# v5.net
KiCad netlist of a schematic drawn in EAGLE
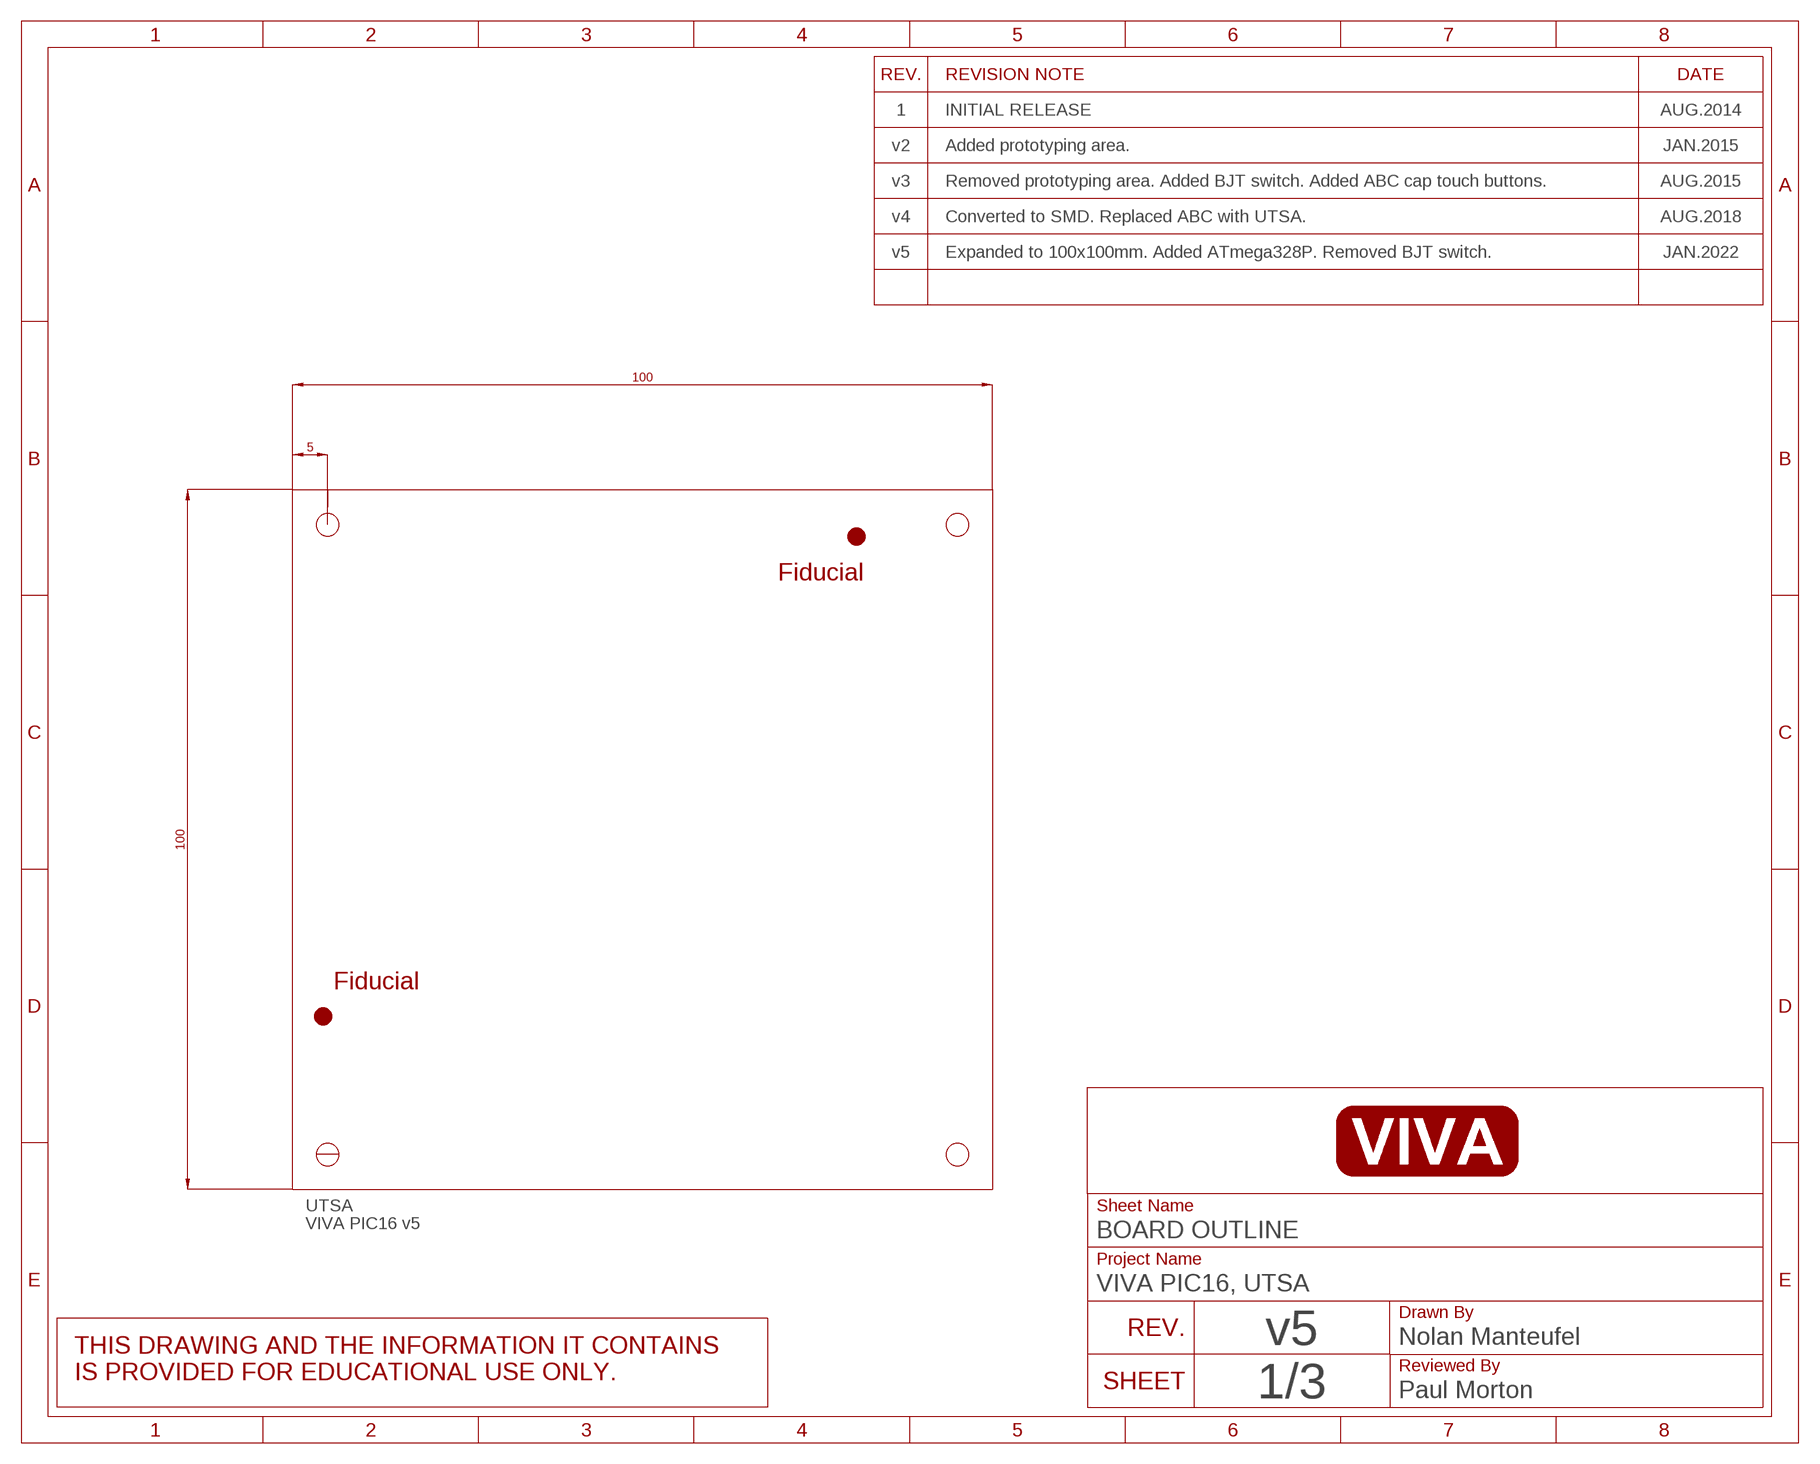
[diagram p0: schematic, sheet 1]
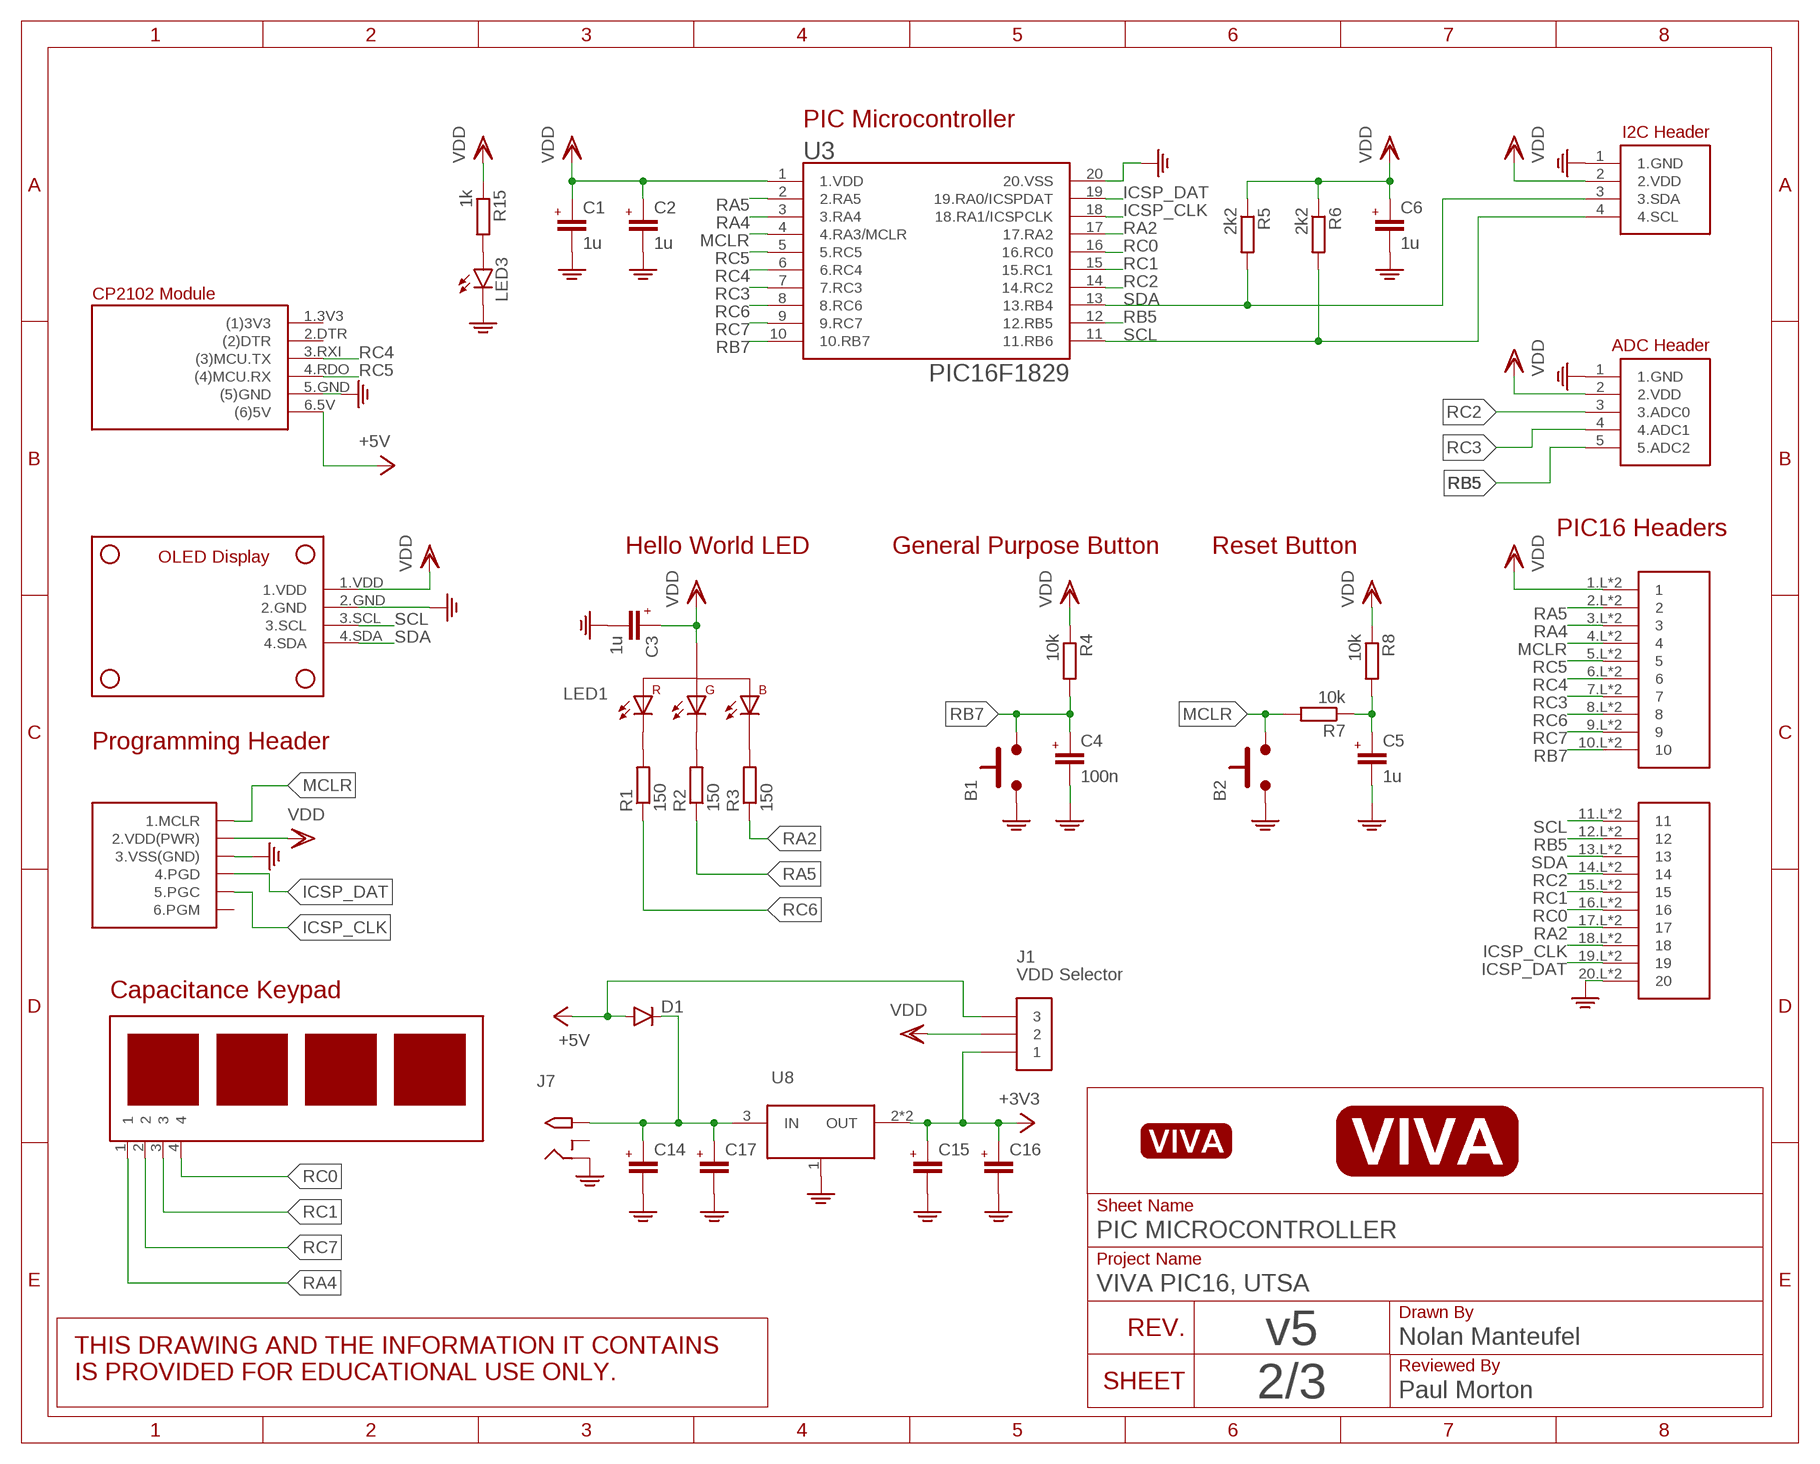
[diagram p1: schematic, sheet 2]
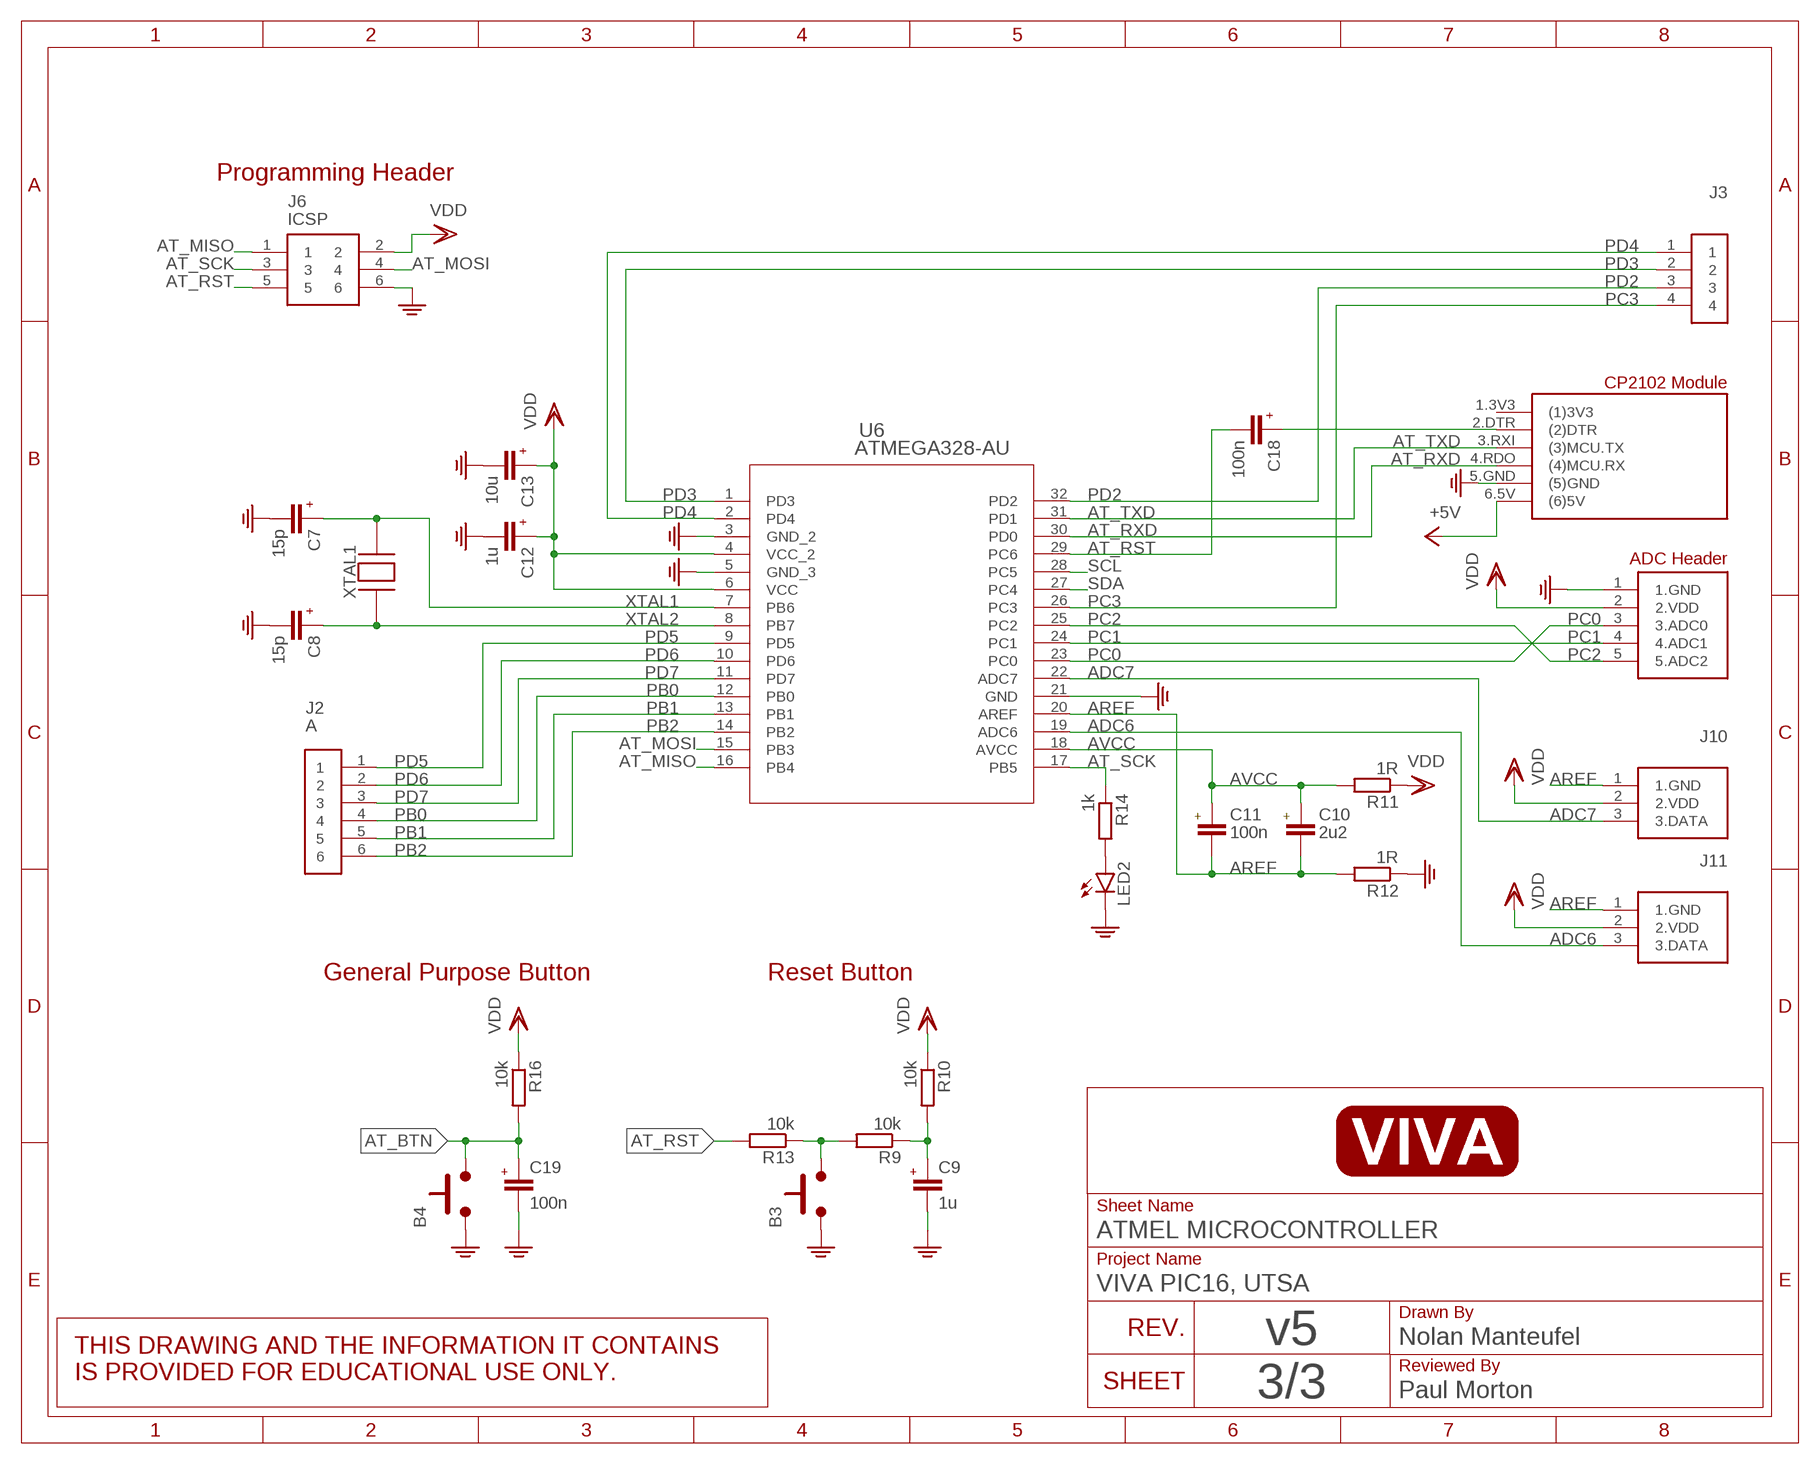
[diagram p2: schematic, sheet 3]

(export (version "E")
  (design (tool "Eeschema 10.0.6"))
  (components
    (comp (ref "A1")
      (value "FIDUCIAL")
      (footprint "eagle-import:FIDUCIAL")
      (libsource (lib "eagle-import") (part "FIDUCIAL"))
    )
    (comp (ref "A2")
      (value "FIDUCIAL")
      (footprint "eagle-import:FIDUCIAL")
      (libsource (lib "eagle-import") (part "FIDUCIAL"))
    )
    (comp (ref "UTSA")
      (value "VIVA PIC16 v5")
      (footprint "eagle-import:PCB_100X100")
      (libsource (lib "eagle-import") (part "PCB_100X100"))
    )
    (comp (ref "B3")
      (value "PUSHBUTTON6X6MM")
      (footprint "eagle-import:6X6MM")
      (libsource (lib "eagle-import") (part "PUSHBUTTON6X6MM"))
    )
    (comp (ref "B4")
      (value "PUSHBUTTON6X6MM")
      (footprint "eagle-import:6X6MM")
      (libsource (lib "eagle-import") (part "PUSHBUTTON6X6MM"))
    )
    (comp (ref "C7")
      (value "15p")
      (footprint "eagle-import:C0603")
      (libsource (lib "eagle-import") (part "C0603"))
    )
    (comp (ref "C8")
      (value "15p")
      (footprint "eagle-import:C0603")
      (libsource (lib "eagle-import") (part "C0603"))
    )
    (comp (ref "C9")
      (value "1u")
      (footprint "eagle-import:C0805")
      (libsource (lib "eagle-import") (part "C0805"))
    )
    (comp (ref "C10")
      (value "2u2")
      (footprint "eagle-import:C0805")
      (libsource (lib "eagle-import") (part "C-EU_C0805"))
    )
    (comp (ref "C11")
      (value "100n")
      (footprint "eagle-import:C0805")
      (libsource (lib "eagle-import") (part "C-EU_C0805"))
    )
    (comp (ref "C12")
      (value "1u")
      (footprint "eagle-import:C0805")
      (libsource (lib "eagle-import") (part "C0805"))
    )
    (comp (ref "C13")
      (value "10u")
      (footprint "eagle-import:C0805")
      (libsource (lib "eagle-import") (part "C0805"))
    )
    (comp (ref "C18")
      (value "100n")
      (footprint "eagle-import:C0805")
      (libsource (lib "eagle-import") (part "C0805"))
    )
    (comp (ref "C19")
      (value "100n")
      (footprint "eagle-import:C0805")
      (libsource (lib "eagle-import") (part "C0805"))
    )
    (comp (ref "J2")
      (value "A")
      (footprint "eagle-import:PINS_6")
      (libsource (lib "eagle-import") (part "PINS_6SQUARE"))
    )
    (comp (ref "J3")
      (value "PINS_4_0100")
      (footprint "eagle-import:PINS_4")
      (libsource (lib "eagle-import") (part "PINS_4_0100"))
    )
    (comp (ref "J6")
      (value "ICSP")
      (footprint "eagle-import:PINS_6-2X3")
      (libsource (lib "eagle-import") (part "PINS_6-2X3"))
    )
    (comp (ref "J9")
      (value "VIVA-HEADER-ADC-PIC16")
      (footprint "eagle-import:VIVA-HEADER-ADC-PIC16")
      (libsource (lib "eagle-import") (part "VIVA-HEADER-ADC-PIC16"))
    )
    (comp (ref "J10")
      (value "VIVA-HEADER-GPIO-1")
      (footprint "eagle-import:VIVA-HEADER-GPIO-RA-1")
      (libsource (lib "eagle-import") (part "VIVA-HEADER-GPIO-1"))
    )
    (comp (ref "J11")
      (value "VIVA-HEADER-GPIO-1")
      (footprint "eagle-import:VIVA-HEADER-GPIO-RA-1")
      (libsource (lib "eagle-import") (part "VIVA-HEADER-GPIO-1"))
    )
    (comp (ref "LED2")
      (value "LEDSML0805")
      (footprint "eagle-import:SML0805")
      (libsource (lib "eagle-import") (part "LEDSML0805"))
    )
    (comp (ref "R9")
      (value "10k")
      (footprint "eagle-import:R0805")
      (libsource (lib "eagle-import") (part "R-EU__R0805"))
    )
    (comp (ref "R10")
      (value "10k")
      (footprint "eagle-import:R0805")
      (libsource (lib "eagle-import") (part "R-EU__R0805"))
    )
    (comp (ref "R11")
      (value "1R")
      (footprint "eagle-import:R0805")
      (libsource (lib "eagle-import") (part "R-EU__R0805"))
    )
    (comp (ref "R12")
      (value "1R")
      (footprint "eagle-import:R0805")
      (libsource (lib "eagle-import") (part "R-EU__R0805"))
    )
    (comp (ref "R13")
      (value "10k")
      (footprint "eagle-import:R0805")
      (libsource (lib "eagle-import") (part "R-EU__R0805"))
    )
    (comp (ref "R14")
      (value "1k")
      (footprint "eagle-import:R0805")
      (libsource (lib "eagle-import") (part "R-EU__R0805"))
    )
    (comp (ref "R16")
      (value "10k")
      (footprint "eagle-import:R0805")
      (libsource (lib "eagle-import") (part "R-EU__R0805"))
    )
    (comp (ref "U6")
      (value "ATMEGA328-AU")
      (footprint "eagle-import:32A_ATM")
      (fields (field (name "COPYRIGHT") "Copyright (C) 2021 Ultra Librarian. All rights reserved."))
      (libsource (lib "eagle-import") (part "ATMEGA328-AU"))
    )
    (comp (ref "U7")
      (value "VIVA_USB-TTL")
      (footprint "eagle-import:VIVA_USB_TTL_SUBTEXT")
      (libsource (lib "eagle-import") (part "VIVA_USB-TTL"))
    )
    (comp (ref "XTAL1")
      (value "CRYSTAL-SMD")
      (footprint "eagle-import:HC49S-SMD")
      (libsource (lib "eagle-import") (part "CRYSTAL-SMD"))
    )
    (comp (ref "B1")
      (value "PUSHBUTTON6X6MM")
      (footprint "eagle-import:6X6MM")
      (libsource (lib "eagle-import") (part "PUSHBUTTON6X6MM"))
    )
    (comp (ref "B2")
      (value "PUSHBUTTON6X6MM")
      (footprint "eagle-import:6X6MM")
      (libsource (lib "eagle-import") (part "PUSHBUTTON6X6MM"))
    )
    (comp (ref "C1")
      (value "1u")
      (footprint "eagle-import:C0805")
      (libsource (lib "eagle-import") (part "C0805"))
    )
    (comp (ref "C2")
      (value "1u")
      (footprint "eagle-import:C0805")
      (libsource (lib "eagle-import") (part "C0805"))
    )
    (comp (ref "C3")
      (value "1u")
      (footprint "eagle-import:C0805")
      (libsource (lib "eagle-import") (part "C0805"))
    )
    (comp (ref "C4")
      (value "100n")
      (footprint "eagle-import:C0805")
      (libsource (lib "eagle-import") (part "C0805"))
    )
    (comp (ref "C5")
      (value "1u")
      (footprint "eagle-import:C0805")
      (libsource (lib "eagle-import") (part "C0805"))
    )
    (comp (ref "C6")
      (value "1u")
      (footprint "eagle-import:C0805")
      (libsource (lib "eagle-import") (part "C0805"))
    )
    (comp (ref "C14")
      (value "C0805")
      (footprint "eagle-import:C0805")
      (libsource (lib "eagle-import") (part "C0805"))
    )
    (comp (ref "C15")
      (value "C0805")
      (footprint "eagle-import:C0805")
      (libsource (lib "eagle-import") (part "C0805"))
    )
    (comp (ref "C16")
      (value "C0805")
      (footprint "eagle-import:C0805")
      (libsource (lib "eagle-import") (part "C0805"))
    )
    (comp (ref "C17")
      (value "C0805")
      (footprint "eagle-import:C0805")
      (libsource (lib "eagle-import") (part "C0805"))
    )
    (comp (ref "D1")
      (value "DIODE-DO214AC")
      (footprint "eagle-import:DO214AC")
      (libsource (lib "eagle-import") (part "DIODE-DO214AC"))
    )
    (comp (ref "J1")
      (value "VDD Selector")
      (footprint "eagle-import:PINS_3")
      (libsource (lib "eagle-import") (part "PINS_3_2.54"))
    )
    (comp (ref "J4")
      (value "PICKIT3")
      (footprint "eagle-import:PICKIT3")
      (libsource (lib "eagle-import") (part "PICKIT3"))
    )
    (comp (ref "J5")
      (value "VIVA-HEADER-ADC-PIC16")
      (footprint "eagle-import:VIVA-HEADER-ADC-PIC16")
      (libsource (lib "eagle-import") (part "VIVA-HEADER-ADC-PIC16"))
    )
    (comp (ref "J7")
      (value "2.1MMJACKTHM")
      (footprint "eagle-import:PJ-102A")
      (libsource (lib "eagle-import") (part "2.1MMJACKTHM"))
    )
    (comp (ref "LED1")
      (value "LED_RGBLTST-C19FD1WT")
      (footprint "eagle-import:0805_RGB")
      (libsource (lib "eagle-import") (part "LED_RGBLTST-C19FD1WT"))
    )
    (comp (ref "LED3")
      (value "LEDSML0805")
      (footprint "eagle-import:SML0805")
      (libsource (lib "eagle-import") (part "LEDSML0805"))
    )
    (comp (ref "R1")
      (value "150")
      (footprint "eagle-import:R0805")
      (libsource (lib "eagle-import") (part "R-EU__R0805"))
    )
    (comp (ref "R2")
      (value "150")
      (footprint "eagle-import:R0805")
      (libsource (lib "eagle-import") (part "R-EU__R0805"))
    )
    (comp (ref "R3")
      (value "150")
      (footprint "eagle-import:R0805")
      (libsource (lib "eagle-import") (part "R-EU__R0805"))
    )
    (comp (ref "R4")
      (value "10k")
      (footprint "eagle-import:R0805")
      (libsource (lib "eagle-import") (part "R-EU__R0805"))
    )
    (comp (ref "R5")
      (value "2k2")
      (footprint "eagle-import:R0805")
      (libsource (lib "eagle-import") (part "R-EU__R0805"))
    )
    (comp (ref "R6")
      (value "2k2")
      (footprint "eagle-import:R0805")
      (libsource (lib "eagle-import") (part "R-EU__R0805"))
    )
    (comp (ref "R7")
      (value "10k")
      (footprint "eagle-import:R0805")
      (libsource (lib "eagle-import") (part "R-EU__R0805"))
    )
    (comp (ref "R8")
      (value "10k")
      (footprint "eagle-import:R0805")
      (libsource (lib "eagle-import") (part "R-EU__R0805"))
    )
    (comp (ref "R15")
      (value "1k")
      (footprint "eagle-import:R0805")
      (libsource (lib "eagle-import") (part "R-EU__R0805"))
    )
    (comp (ref "U$2")
      (value "VIVA_LOGO")
      (footprint "eagle-import:VIVA_LOGO")
      (libsource (lib "eagle-import") (part "VIVA_LOGO"))
    )
    (comp (ref "U$3")
      (value "VIVA_OLED")
      (footprint "eagle-import:VIVA_OLED-I2C")
      (libsource (lib "eagle-import") (part "VIVA_OLED"))
    )
    (comp (ref "U1")
      (value "VIVA_UTSA-KEYPADV5")
      (footprint "eagle-import:VIVA_UTSA-KEYPAD-V5")
      (libsource (lib "eagle-import") (part "VIVA_UTSA-KEYPADV5"))
    )
    (comp (ref "U2")
      (value "VIVA_USB-TTL")
      (footprint "eagle-import:VIVA_USB_TTL_SUBTEXT")
      (libsource (lib "eagle-import") (part "VIVA_USB-TTL"))
    )
    (comp (ref "U3")
      (value "PIC16F1829")
      (footprint "eagle-import:SOP20-NEW")
      (libsource (lib "eagle-import") (part "PIC16F1829300"))
    )
    (comp (ref "U4")
      (value "VIVA-HEADER-I2C-RA")
      (footprint "eagle-import:VIVA-HEADER-I2C-RA")
      (libsource (lib "eagle-import") (part "VIVA-HEADER-I2C-RA"))
    )
    (comp (ref "U5")
      (value "VIVA_PIC16BOARD")
      (footprint "eagle-import:VIVA_PIC16")
      (libsource (lib "eagle-import") (part "VIVA_PIC16BOARD"))
    )
    (comp (ref "U8")
      (value "REGULATOR_SCHLM1117")
      (footprint "eagle-import:SOT223")
      (libsource (lib "eagle-import") (part "REGULATOR_SCHLM1117"))
    )
  )
  (nets
    (net (code "1") (name "+3V3") (class "Default")
      (node (ref "C15") (pin "2") (pinfunction "+_2") (pintype "passive"))
      (node (ref "C16") (pin "2") (pinfunction "+_2") (pintype "passive"))
      (node (ref "J1") (pin "1") (pinfunction "1_1") (pintype "bidirectional"))
      (node (ref "U8") (pin "2") (pinfunction "OUT_2") (pintype "bidirectional"))
      (node (ref "U8") (pin "4.TAB") (pinfunction "OUT_4.TAB") (pintype "bidirectional"))
    )
    (net (code "2") (name "+5V") (class "Default")
      (node (ref "D1") (pin "A") (pinfunction "A_A") (pintype "passive"))
      (node (ref "J1") (pin "3") (pinfunction "3_3") (pintype "bidirectional"))
      (node (ref "U2") (pin "6.5V") (pinfunction "(6)5V_6.5V") (pintype "bidirectional"))
      (node (ref "U7") (pin "6.5V") (pinfunction "(6)5V_6.5V") (pintype "bidirectional"))
    )
    (net (code "3") (name "ADC6") (class "Default")
      (node (ref "J11") (pin "3") (pinfunction "3.DATA_3") (pintype "bidirectional"))
      (node (ref "U6") (pin "19") (pinfunction "ADC6_19") (pintype "passive"))
    )
    (net (code "4") (name "ADC7") (class "Default")
      (node (ref "J10") (pin "3") (pinfunction "3.DATA_3") (pintype "bidirectional"))
      (node (ref "U6") (pin "22") (pinfunction "ADC7_22") (pintype "passive"))
    )
    (net (code "5") (name "AREF") (class "Default")
      (node (ref "C10") (pin "2") (pinfunction "2_2") (pintype "passive"))
      (node (ref "C11") (pin "2") (pinfunction "2_2") (pintype "passive"))
      (node (ref "J10") (pin "1") (pinfunction "1.GND_1") (pintype "bidirectional"))
      (node (ref "J11") (pin "1") (pinfunction "1.GND_1") (pintype "bidirectional"))
      (node (ref "R12") (pin "2") (pinfunction "2_2") (pintype "passive"))
      (node (ref "U6") (pin "20") (pinfunction "AREF_20") (pintype "passive"))
    )
    (net (code "6") (name "AT_BTN") (class "Default")
      (node (ref "B4") (pin "3.B") (pinfunction "2_3.B") (pintype "bidirectional"))
      (node (ref "B4") (pin "4.B") (pinfunction "2_4.B") (pintype "bidirectional"))
      (node (ref "C19") (pin "2") (pinfunction "+_2") (pintype "passive"))
      (node (ref "R16") (pin "2") (pinfunction "2_2") (pintype "passive"))
    )
    (net (code "7") (name "AT_MISO") (class "Default")
      (node (ref "J6") (pin "1") (pinfunction "1_1") (pintype "bidirectional"))
      (node (ref "U6") (pin "16") (pinfunction "PB4_16") (pintype "bidirectional"))
    )
    (net (code "8") (name "AT_MOSI") (class "Default")
      (node (ref "J6") (pin "4") (pinfunction "4_4") (pintype "bidirectional"))
      (node (ref "U6") (pin "15") (pinfunction "PB3_15") (pintype "bidirectional"))
    )
    (net (code "9") (name "AT_RST") (class "Default")
      (node (ref "C18") (pin "1") (pinfunction "-_1") (pintype "passive"))
      (node (ref "J6") (pin "5") (pinfunction "5_5") (pintype "bidirectional"))
      (node (ref "R13") (pin "2") (pinfunction "2_2") (pintype "passive"))
      (node (ref "U6") (pin "29") (pinfunction "PC6_29") (pintype "bidirectional"))
    )
    (net (code "10") (name "AT_RXD") (class "Default")
      (node (ref "U6") (pin "30") (pinfunction "PD0_30") (pintype "bidirectional"))
      (node (ref "U7") (pin "4.RDO") (pinfunction "(4)MCU.RX_4.RDO") (pintype "bidirectional"))
    )
    (net (code "11") (name "AT_SCK") (class "Default")
      (node (ref "J6") (pin "3") (pinfunction "3_3") (pintype "bidirectional"))
      (node (ref "R14") (pin "1") (pinfunction "1_1") (pintype "passive"))
      (node (ref "U6") (pin "17") (pinfunction "PB5_17") (pintype "bidirectional"))
    )
    (net (code "12") (name "AT_TXD") (class "Default")
      (node (ref "U6") (pin "31") (pinfunction "PD1_31") (pintype "bidirectional"))
      (node (ref "U7") (pin "3.RXI") (pinfunction "(3)MCU.TX_3.RXI") (pintype "bidirectional"))
    )
    (net (code "13") (name "AVCC") (class "Default")
      (node (ref "C10") (pin "1") (pinfunction "1_1") (pintype "passive"))
      (node (ref "C11") (pin "1") (pinfunction "1_1") (pintype "passive"))
      (node (ref "R11") (pin "2") (pinfunction "2_2") (pintype "passive"))
      (node (ref "U6") (pin "18") (pinfunction "AVCC_18") (pintype "power_in"))
    )
    (net (code "14") (name "GND") (class "Default")
      (node (ref "B1") (pin "1.A") (pinfunction "1_1.A") (pintype "bidirectional"))
      (node (ref "B1") (pin "2.A") (pinfunction "1_2.A") (pintype "bidirectional"))
      (node (ref "B2") (pin "1.A") (pinfunction "1_1.A") (pintype "bidirectional"))
      (node (ref "B2") (pin "2.A") (pinfunction "1_2.A") (pintype "bidirectional"))
      (node (ref "B3") (pin "1.A") (pinfunction "1_1.A") (pintype "bidirectional"))
      (node (ref "B3") (pin "2.A") (pinfunction "1_2.A") (pintype "bidirectional"))
      (node (ref "B4") (pin "1.A") (pinfunction "1_1.A") (pintype "bidirectional"))
      (node (ref "B4") (pin "2.A") (pinfunction "1_2.A") (pintype "bidirectional"))
      (node (ref "C1") (pin "1") (pinfunction "-_1") (pintype "passive"))
      (node (ref "C12") (pin "1") (pinfunction "-_1") (pintype "passive"))
      (node (ref "C13") (pin "1") (pinfunction "-_1") (pintype "passive"))
      (node (ref "C14") (pin "1") (pinfunction "-_1") (pintype "passive"))
      (node (ref "C15") (pin "1") (pinfunction "-_1") (pintype "passive"))
      (node (ref "C16") (pin "1") (pinfunction "-_1") (pintype "passive"))
      (node (ref "C17") (pin "1") (pinfunction "-_1") (pintype "passive"))
      (node (ref "C19") (pin "1") (pinfunction "-_1") (pintype "passive"))
      (node (ref "C2") (pin "1") (pinfunction "-_1") (pintype "passive"))
      (node (ref "C3") (pin "1") (pinfunction "-_1") (pintype "passive"))
      (node (ref "C4") (pin "1") (pinfunction "-_1") (pintype "passive"))
      (node (ref "C5") (pin "1") (pinfunction "-_1") (pintype "passive"))
      (node (ref "C6") (pin "1") (pinfunction "-_1") (pintype "passive"))
      (node (ref "C7") (pin "1") (pinfunction "-_1") (pintype "passive"))
      (node (ref "C8") (pin "1") (pinfunction "-_1") (pintype "passive"))
      (node (ref "C9") (pin "1") (pinfunction "-_1") (pintype "passive"))
      (node (ref "J4") (pin "3") (pinfunction "3.VSS(GND)_3") (pintype "bidirectional"))
      (node (ref "J5") (pin "1") (pinfunction "1.GND_1") (pintype "bidirectional"))
      (node (ref "J6") (pin "6") (pinfunction "6_6") (pintype "bidirectional"))
      (node (ref "J7") (pin "RING") (pinfunction "RING_RING") (pintype "bidirectional"))
      (node (ref "J9") (pin "1") (pinfunction "1.GND_1") (pintype "bidirectional"))
      (node (ref "LED2") (pin "C") (pinfunction "C_C") (pintype "passive"))
      (node (ref "LED3") (pin "C") (pinfunction "C_C") (pintype "passive"))
      (node (ref "R12") (pin "1") (pinfunction "1_1") (pintype "passive"))
      (node (ref "U$3") (pin "2.GND") (pinfunction "2.GND_2.GND") (pintype "bidirectional"))
      (node (ref "U2") (pin "5.GND") (pinfunction "(5)GND_5.GND") (pintype "bidirectional"))
      (node (ref "U3") (pin "20") (pinfunction "20.VSS_20") (pintype "bidirectional"))
      (node (ref "U4") (pin "1") (pinfunction "1.GND_1") (pintype "bidirectional"))
      (node (ref "U5") (pin "20.L") (pinfunction "20_20.L") (pintype "bidirectional"))
      (node (ref "U5") (pin "20.R") (pinfunction "20_20.R") (pintype "bidirectional"))
      (node (ref "U6") (pin "21") (pinfunction "GND_21") (pintype "power_in"))
      (node (ref "U6") (pin "3") (pinfunction "GND_2_3") (pintype "power_in"))
      (node (ref "U6") (pin "5") (pinfunction "GND_3_5") (pintype "power_in"))
      (node (ref "U7") (pin "5.GND") (pinfunction "(5)GND_5.GND") (pintype "bidirectional"))
      (node (ref "U8") (pin "1") (pinfunction "GND_1") (pintype "bidirectional"))
    )
    (net (code "15") (name "ICSP_CLK") (class "Default")
      (node (ref "J4") (pin "5") (pinfunction "5.PGC_5") (pintype "bidirectional"))
      (node (ref "U3") (pin "18") (pinfunction "18.RA1/ICSPCLK_18") (pintype "bidirectional"))
      (node (ref "U5") (pin "18.L") (pinfunction "18_18.L") (pintype "bidirectional"))
      (node (ref "U5") (pin "18.R") (pinfunction "18_18.R") (pintype "bidirectional"))
    )
    (net (code "16") (name "ICSP_DAT") (class "Default")
      (node (ref "J4") (pin "4") (pinfunction "4.PGD_4") (pintype "bidirectional"))
      (node (ref "U3") (pin "19") (pinfunction "19.RA0/ICSPDAT_19") (pintype "bidirectional"))
      (node (ref "U5") (pin "19.L") (pinfunction "19_19.L") (pintype "bidirectional"))
      (node (ref "U5") (pin "19.R") (pinfunction "19_19.R") (pintype "bidirectional"))
    )
    (net (code "17") (name "MCLR") (class "Default")
      (node (ref "B2") (pin "3.B") (pinfunction "2_3.B") (pintype "bidirectional"))
      (node (ref "B2") (pin "4.B") (pinfunction "2_4.B") (pintype "bidirectional"))
      (node (ref "J4") (pin "1") (pinfunction "1.MCLR_1") (pintype "bidirectional"))
      (node (ref "R7") (pin "2") (pinfunction "2_2") (pintype "passive"))
      (node (ref "U3") (pin "4") (pinfunction "4.RA3/MCLR_4") (pintype "bidirectional"))
      (node (ref "U5") (pin "4.L") (pinfunction "4_4.L") (pintype "bidirectional"))
      (node (ref "U5") (pin "4.R") (pinfunction "4_4.R") (pintype "bidirectional"))
    )
    (net (code "18") (name "Net-(B3-2-Pad3.B)") (class "Default")
      (node (ref "B3") (pin "3.B") (pinfunction "2_3.B") (pintype "bidirectional"))
      (node (ref "B3") (pin "4.B") (pinfunction "2_4.B") (pintype "bidirectional"))
      (node (ref "R13") (pin "1") (pinfunction "1_1") (pintype "passive"))
      (node (ref "R9") (pin "2") (pinfunction "2_2") (pintype "passive"))
    )
    (net (code "19") (name "Net-(C5-+)") (class "Default")
      (node (ref "C5") (pin "2") (pinfunction "+_2") (pintype "passive"))
      (node (ref "R7") (pin "1") (pinfunction "1_1") (pintype "passive"))
      (node (ref "R8") (pin "2") (pinfunction "2_2") (pintype "passive"))
    )
    (net (code "20") (name "Net-(C9-+)") (class "Default")
      (node (ref "C9") (pin "2") (pinfunction "+_2") (pintype "passive"))
      (node (ref "R10") (pin "2") (pinfunction "2_2") (pintype "passive"))
      (node (ref "R9") (pin "1") (pinfunction "1_1") (pintype "passive"))
    )
    (net (code "21") (name "Net-(C14-+)") (class "Default")
      (node (ref "C14") (pin "2") (pinfunction "+_2") (pintype "passive"))
      (node (ref "C17") (pin "2") (pinfunction "+_2") (pintype "passive"))
      (node (ref "D1") (pin "C") (pinfunction "C_C") (pintype "passive"))
      (node (ref "J7") (pin "TIP") (pinfunction "TIP_TIP") (pintype "bidirectional"))
      (node (ref "U8") (pin "3") (pinfunction "IN_3") (pintype "bidirectional"))
    )
    (net (code "22") (name "Net-(C18-+)") (class "Default")
      (node (ref "C18") (pin "2") (pinfunction "+_2") (pintype "passive"))
      (node (ref "U7") (pin "2.DTR") (pinfunction "(2)DTR_2.DTR") (pintype "bidirectional"))
    )
    (net (code "23") (name "Net-(LED1-1.R-)") (class "Default")
      (node (ref "LED1") (pin "2") (pinfunction "1.R-_2") (pintype "passive"))
      (node (ref "R1") (pin "2") (pinfunction "2_2") (pintype "passive"))
    )
    (net (code "24") (name "Net-(LED1-2.G-)") (class "Default")
      (node (ref "LED1") (pin "3") (pinfunction "2.G-_3") (pintype "passive"))
      (node (ref "R2") (pin "2") (pinfunction "2_2") (pintype "passive"))
    )
    (net (code "25") (name "Net-(LED1-4.B-)") (class "Default")
      (node (ref "LED1") (pin "1") (pinfunction "4.B-_1") (pintype "passive"))
      (node (ref "R3") (pin "2") (pinfunction "2_2") (pintype "passive"))
    )
    (net (code "26") (name "Net-(LED2-PadA)") (class "Default")
      (node (ref "LED2") (pin "A") (pinfunction "A_A") (pintype "passive"))
      (node (ref "R14") (pin "2") (pinfunction "2_2") (pintype "passive"))
    )
    (net (code "27") (name "Net-(LED3-PadA)") (class "Default")
      (node (ref "LED3") (pin "A") (pinfunction "A_A") (pintype "passive"))
      (node (ref "R15") (pin "2") (pinfunction "2_2") (pintype "passive"))
    )
    (net (code "28") (name "PB0") (class "Default")
      (node (ref "J2") (pin "4") (pinfunction "4_4") (pintype "bidirectional"))
      (node (ref "U6") (pin "12") (pinfunction "PB0_12") (pintype "bidirectional"))
    )
    (net (code "29") (name "PB1") (class "Default")
      (node (ref "J2") (pin "5") (pinfunction "5_5") (pintype "bidirectional"))
      (node (ref "U6") (pin "13") (pinfunction "PB1_13") (pintype "bidirectional"))
    )
    (net (code "30") (name "PB2") (class "Default")
      (node (ref "J2") (pin "6") (pinfunction "6_6") (pintype "bidirectional"))
      (node (ref "U6") (pin "14") (pinfunction "PB2_14") (pintype "bidirectional"))
    )
    (net (code "31") (name "PC0") (class "Default")
      (node (ref "J9") (pin "3") (pinfunction "3.ADC0_3") (pintype "bidirectional"))
      (node (ref "U6") (pin "23") (pinfunction "PC0_23") (pintype "bidirectional"))
    )
    (net (code "32") (name "PC1") (class "Default")
      (node (ref "J9") (pin "4") (pinfunction "4.ADC1_4") (pintype "bidirectional"))
      (node (ref "U6") (pin "24") (pinfunction "PC1_24") (pintype "bidirectional"))
    )
    (net (code "33") (name "PC2") (class "Default")
      (node (ref "J9") (pin "5") (pinfunction "5.ADC2_5") (pintype "bidirectional"))
      (node (ref "U6") (pin "25") (pinfunction "PC2_25") (pintype "bidirectional"))
    )
    (net (code "34") (name "PC3") (class "Default")
      (node (ref "J3") (pin "4") (pinfunction "4_4") (pintype "bidirectional"))
      (node (ref "U6") (pin "26") (pinfunction "PC3_26") (pintype "bidirectional"))
    )
    (net (code "35") (name "PD2") (class "Default")
      (node (ref "J3") (pin "3") (pinfunction "3_3") (pintype "bidirectional"))
      (node (ref "U6") (pin "32") (pinfunction "PD2_32") (pintype "bidirectional"))
    )
    (net (code "36") (name "PD3") (class "Default")
      (node (ref "J3") (pin "2") (pinfunction "2_2") (pintype "bidirectional"))
      (node (ref "U6") (pin "1") (pinfunction "PD3_1") (pintype "bidirectional"))
    )
    (net (code "37") (name "PD4") (class "Default")
      (node (ref "J3") (pin "1") (pinfunction "1_1") (pintype "bidirectional"))
      (node (ref "U6") (pin "2") (pinfunction "PD4_2") (pintype "bidirectional"))
    )
    (net (code "38") (name "PD5") (class "Default")
      (node (ref "J2") (pin "1") (pinfunction "1_1") (pintype "bidirectional"))
      (node (ref "U6") (pin "9") (pinfunction "PD5_9") (pintype "bidirectional"))
    )
    (net (code "39") (name "PD6") (class "Default")
      (node (ref "J2") (pin "2") (pinfunction "2_2") (pintype "bidirectional"))
      (node (ref "U6") (pin "10") (pinfunction "PD6_10") (pintype "bidirectional"))
    )
    (net (code "40") (name "PD7") (class "Default")
      (node (ref "J2") (pin "3") (pinfunction "3_3") (pintype "bidirectional"))
      (node (ref "U6") (pin "11") (pinfunction "PD7_11") (pintype "bidirectional"))
    )
    (net (code "41") (name "RA2") (class "Default")
      (node (ref "R3") (pin "1") (pinfunction "1_1") (pintype "passive"))
      (node (ref "U3") (pin "17") (pinfunction "17.RA2_17") (pintype "bidirectional"))
      (node (ref "U5") (pin "17.L") (pinfunction "17_17.L") (pintype "bidirectional"))
      (node (ref "U5") (pin "17.R") (pinfunction "17_17.R") (pintype "bidirectional"))
    )
    (net (code "42") (name "RA4") (class "Default")
      (node (ref "U1") (pin "1") (pinfunction "1_1") (pintype "bidirectional"))
      (node (ref "U3") (pin "3") (pinfunction "3.RA4_3") (pintype "bidirectional"))
      (node (ref "U5") (pin "3.L") (pinfunction "3_3.L") (pintype "bidirectional"))
      (node (ref "U5") (pin "3.R") (pinfunction "3_3.R") (pintype "bidirectional"))
    )
    (net (code "43") (name "RA5") (class "Default")
      (node (ref "R2") (pin "1") (pinfunction "1_1") (pintype "passive"))
      (node (ref "U3") (pin "2") (pinfunction "2.RA5_2") (pintype "bidirectional"))
      (node (ref "U5") (pin "2.L") (pinfunction "2_2.L") (pintype "bidirectional"))
      (node (ref "U5") (pin "2.R") (pinfunction "2_2.R") (pintype "bidirectional"))
    )
    (net (code "44") (name "RB5") (class "Default")
      (node (ref "J5") (pin "5") (pinfunction "5.ADC2_5") (pintype "bidirectional"))
      (node (ref "U3") (pin "12") (pinfunction "12.RB5_12") (pintype "bidirectional"))
      (node (ref "U5") (pin "12.L") (pinfunction "12_12.L") (pintype "bidirectional"))
      (node (ref "U5") (pin "12.R") (pinfunction "12_12.R") (pintype "bidirectional"))
    )
    (net (code "45") (name "RB7") (class "Default")
      (node (ref "B1") (pin "3.B") (pinfunction "2_3.B") (pintype "bidirectional"))
      (node (ref "B1") (pin "4.B") (pinfunction "2_4.B") (pintype "bidirectional"))
      (node (ref "C4") (pin "2") (pinfunction "+_2") (pintype "passive"))
      (node (ref "R4") (pin "2") (pinfunction "2_2") (pintype "passive"))
      (node (ref "U3") (pin "10") (pinfunction "10.RB7_10") (pintype "bidirectional"))
      (node (ref "U5") (pin "10.L") (pinfunction "10_10.L") (pintype "bidirectional"))
      (node (ref "U5") (pin "10.R") (pinfunction "10_10.R") (pintype "bidirectional"))
    )
    (net (code "46") (name "RC0") (class "Default")
      (node (ref "U1") (pin "4") (pinfunction "4_4") (pintype "bidirectional"))
      (node (ref "U3") (pin "16") (pinfunction "16.RC0_16") (pintype "bidirectional"))
      (node (ref "U5") (pin "16.L") (pinfunction "16_16.L") (pintype "bidirectional"))
      (node (ref "U5") (pin "16.R") (pinfunction "16_16.R") (pintype "bidirectional"))
    )
    (net (code "47") (name "RC1") (class "Default")
      (node (ref "U1") (pin "3") (pinfunction "3_3") (pintype "bidirectional"))
      (node (ref "U3") (pin "15") (pinfunction "15.RC1_15") (pintype "bidirectional"))
      (node (ref "U5") (pin "15.L") (pinfunction "15_15.L") (pintype "bidirectional"))
      (node (ref "U5") (pin "15.R") (pinfunction "15_15.R") (pintype "bidirectional"))
    )
    (net (code "48") (name "RC2") (class "Default")
      (node (ref "J5") (pin "3") (pinfunction "3.ADC0_3") (pintype "bidirectional"))
      (node (ref "U3") (pin "14") (pinfunction "14.RC2_14") (pintype "bidirectional"))
      (node (ref "U5") (pin "14.L") (pinfunction "14_14.L") (pintype "bidirectional"))
      (node (ref "U5") (pin "14.R") (pinfunction "14_14.R") (pintype "bidirectional"))
    )
    (net (code "49") (name "RC3") (class "Default")
      (node (ref "J5") (pin "4") (pinfunction "4.ADC1_4") (pintype "bidirectional"))
      (node (ref "U3") (pin "7") (pinfunction "7.RC3_7") (pintype "bidirectional"))
      (node (ref "U5") (pin "7.L") (pinfunction "7_7.L") (pintype "bidirectional"))
      (node (ref "U5") (pin "7.R") (pinfunction "7_7.R") (pintype "bidirectional"))
    )
    (net (code "50") (name "RC4") (class "Default")
      (node (ref "U2") (pin "3.RXI") (pinfunction "(3)MCU.TX_3.RXI") (pintype "bidirectional"))
      (node (ref "U3") (pin "6") (pinfunction "6.RC4_6") (pintype "bidirectional"))
      (node (ref "U5") (pin "6.L") (pinfunction "6_6.L") (pintype "bidirectional"))
      (node (ref "U5") (pin "6.R") (pinfunction "6_6.R") (pintype "bidirectional"))
    )
    (net (code "51") (name "RC5") (class "Default")
      (node (ref "U2") (pin "4.RDO") (pinfunction "(4)MCU.RX_4.RDO") (pintype "bidirectional"))
      (node (ref "U3") (pin "5") (pinfunction "5.RC5_5") (pintype "bidirectional"))
      (node (ref "U5") (pin "5.L") (pinfunction "5_5.L") (pintype "bidirectional"))
      (node (ref "U5") (pin "5.R") (pinfunction "5_5.R") (pintype "bidirectional"))
    )
    (net (code "52") (name "RC6") (class "Default")
      (node (ref "R1") (pin "1") (pinfunction "1_1") (pintype "passive"))
      (node (ref "U3") (pin "8") (pinfunction "8.RC6_8") (pintype "bidirectional"))
      (node (ref "U5") (pin "8.L") (pinfunction "8_8.L") (pintype "bidirectional"))
      (node (ref "U5") (pin "8.R") (pinfunction "8_8.R") (pintype "bidirectional"))
    )
    (net (code "53") (name "RC7") (class "Default")
      (node (ref "U1") (pin "2") (pinfunction "2_2") (pintype "bidirectional"))
      (node (ref "U3") (pin "9") (pinfunction "9.RC7_9") (pintype "bidirectional"))
      (node (ref "U5") (pin "9.L") (pinfunction "9_9.L") (pintype "bidirectional"))
      (node (ref "U5") (pin "9.R") (pinfunction "9_9.R") (pintype "bidirectional"))
    )
    (net (code "54") (name "SCL") (class "Default")
      (node (ref "R6") (pin "2") (pinfunction "2_2") (pintype "passive"))
      (node (ref "U$3") (pin "3.SCL") (pinfunction "3.SCL_3.SCL") (pintype "bidirectional"))
      (node (ref "U3") (pin "11") (pinfunction "11.RB6_11") (pintype "bidirectional"))
      (node (ref "U4") (pin "4") (pinfunction "4.SCL_4") (pintype "bidirectional"))
      (node (ref "U5") (pin "11.L") (pinfunction "11_11.L") (pintype "bidirectional"))
      (node (ref "U5") (pin "11.R") (pinfunction "11_11.R") (pintype "bidirectional"))
      (node (ref "U6") (pin "28") (pinfunction "PC5_28") (pintype "bidirectional"))
    )
    (net (code "55") (name "SDA") (class "Default")
      (node (ref "R5") (pin "2") (pinfunction "2_2") (pintype "passive"))
      (node (ref "U$3") (pin "4.SDA") (pinfunction "4.SDA_4.SDA") (pintype "bidirectional"))
      (node (ref "U3") (pin "13") (pinfunction "13.RB4_13") (pintype "bidirectional"))
      (node (ref "U4") (pin "3") (pinfunction "3.SDA_3") (pintype "bidirectional"))
      (node (ref "U5") (pin "13.L") (pinfunction "13_13.L") (pintype "bidirectional"))
      (node (ref "U5") (pin "13.R") (pinfunction "13_13.R") (pintype "bidirectional"))
      (node (ref "U6") (pin "27") (pinfunction "PC4_27") (pintype "bidirectional"))
    )
    (net (code "56") (name "VDD") (class "Default")
      (node (ref "C1") (pin "2") (pinfunction "+_2") (pintype "passive"))
      (node (ref "C12") (pin "2") (pinfunction "+_2") (pintype "passive"))
      (node (ref "C13") (pin "2") (pinfunction "+_2") (pintype "passive"))
      (node (ref "C2") (pin "2") (pinfunction "+_2") (pintype "passive"))
      (node (ref "C3") (pin "2") (pinfunction "+_2") (pintype "passive"))
      (node (ref "C6") (pin "2") (pinfunction "+_2") (pintype "passive"))
      (node (ref "J1") (pin "2") (pinfunction "2_2") (pintype "bidirectional"))
      (node (ref "J10") (pin "2") (pinfunction "2.VDD_2") (pintype "bidirectional"))
      (node (ref "J11") (pin "2") (pinfunction "2.VDD_2") (pintype "bidirectional"))
      (node (ref "J4") (pin "2") (pinfunction "2.VDD(PWR)_2") (pintype "bidirectional"))
      (node (ref "J5") (pin "2") (pinfunction "2.VDD_2") (pintype "bidirectional"))
      (node (ref "J6") (pin "2") (pinfunction "2_2") (pintype "bidirectional"))
      (node (ref "J9") (pin "2") (pinfunction "2.VDD_2") (pintype "bidirectional"))
      (node (ref "LED1") (pin "4") (pinfunction "3.+_4") (pintype "passive"))
      (node (ref "R10") (pin "1") (pinfunction "1_1") (pintype "passive"))
      (node (ref "R11") (pin "1") (pinfunction "1_1") (pintype "passive"))
      (node (ref "R15") (pin "1") (pinfunction "1_1") (pintype "passive"))
      (node (ref "R16") (pin "1") (pinfunction "1_1") (pintype "passive"))
      (node (ref "R4") (pin "1") (pinfunction "1_1") (pintype "passive"))
      (node (ref "R5") (pin "1") (pinfunction "1_1") (pintype "passive"))
      (node (ref "R6") (pin "1") (pinfunction "1_1") (pintype "passive"))
      (node (ref "R8") (pin "1") (pinfunction "1_1") (pintype "passive"))
      (node (ref "U$3") (pin "1.VDD") (pinfunction "1.VDD_1.VDD") (pintype "bidirectional"))
      (node (ref "U3") (pin "1") (pinfunction "1.VDD_1") (pintype "bidirectional"))
      (node (ref "U4") (pin "2") (pinfunction "2.VDD_2") (pintype "bidirectional"))
      (node (ref "U5") (pin "1.L") (pinfunction "1_1.L") (pintype "bidirectional"))
      (node (ref "U5") (pin "1.R") (pinfunction "1_1.R") (pintype "bidirectional"))
      (node (ref "U6") (pin "4") (pinfunction "VCC_2_4") (pintype "power_in"))
      (node (ref "U6") (pin "6") (pinfunction "VCC_6") (pintype "power_in"))
    )
    (net (code "57") (name "XTAL1") (class "Default")
      (node (ref "C7") (pin "2") (pinfunction "+_2") (pintype "passive"))
      (node (ref "U6") (pin "7") (pinfunction "PB6_7") (pintype "bidirectional"))
      (node (ref "XTAL1") (pin "2") (pinfunction "2_2") (pintype "bidirectional"))
      (node (ref "XTAL1") (pin "4") (pinfunction "2_4") (pintype "bidirectional"))
    )
    (net (code "58") (name "XTAL2") (class "Default")
      (node (ref "C8") (pin "2") (pinfunction "+_2") (pintype "passive"))
      (node (ref "U6") (pin "8") (pinfunction "PB7_8") (pintype "bidirectional"))
      (node (ref "XTAL1") (pin "1") (pinfunction "1_1") (pintype "bidirectional"))
      (node (ref "XTAL1") (pin "3") (pinfunction "1_3") (pintype "bidirectional"))
    )
    (net (code "59") (name "unconnected-(J4-6.PGM-Pad6)") (class "Default")
      (node (ref "J4") (pin "6") (pinfunction "6.PGM_6") (pintype "bidirectional"))
    )
    (net (code "60") (name "unconnected-(J7-PadRING_SW)") (class "Default")
      (node (ref "J7") (pin "RING_SW") (pinfunction "RING_SW_RING_SW") (pintype "bidirectional"))
    )
    (net (code "61") (name "unconnected-(U2-(1)3V3-Pad1.3V3)") (class "Default")
      (node (ref "U2") (pin "1.3V3") (pinfunction "(1)3V3_1.3V3") (pintype "bidirectional"))
    )
    (net (code "62") (name "unconnected-(U2-(2)DTR-Pad2.DTR)") (class "Default")
      (node (ref "U2") (pin "2.DTR") (pinfunction "(2)DTR_2.DTR") (pintype "bidirectional"))
    )
    (net (code "63") (name "unconnected-(U7-(1)3V3-Pad1.3V3)") (class "Default")
      (node (ref "U7") (pin "1.3V3") (pinfunction "(1)3V3_1.3V3") (pintype "bidirectional"))
    )
  )
)
